# RFCU_V2_0.net
KiCad netlist of a schematic drawn in Altium Designer
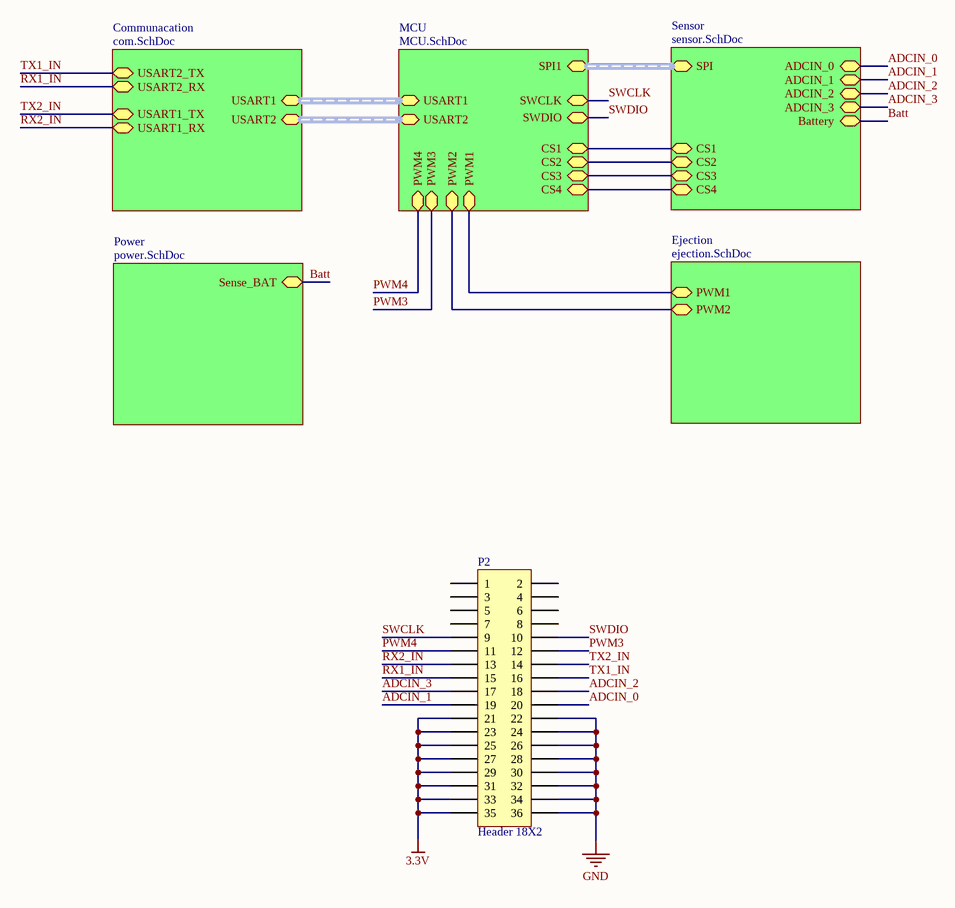
[diagram p0: RFCU_V2.0.SchDoc]

(export (version "E")
  (design (tool "Eeschema 10.0.6"))
  (components
    (comp (ref "P2")
      (value "Header 18X2")
      (footprint "2X18 2.54mm Headers")
      (description "Header, 18-Pin, Dual row")
      (fields (field (name "PUBLISHER") "Altium Limited"))
      (libsource (lib "Miscellaneous Connectors") (part "Header 18X2"))
    )
  )
  (nets
    (net (code "1") (name "/ADCIN_0") (class "Default")
      (node (ref "P2") (pin "20") (pinfunction "20_20") (pintype "passive"))
    )
    (net (code "2") (name "/ADCIN_1") (class "Default")
      (node (ref "P2") (pin "19") (pinfunction "19_19") (pintype "passive"))
    )
    (net (code "3") (name "/ADCIN_2") (class "Default")
      (node (ref "P2") (pin "18") (pinfunction "18_18") (pintype "passive"))
    )
    (net (code "4") (name "/ADCIN_3") (class "Default")
      (node (ref "P2") (pin "17") (pinfunction "17_17") (pintype "passive"))
    )
    (net (code "15") (name "/PWM3") (class "Default")
      (node (ref "P2") (pin "12") (pinfunction "12_12") (pintype "passive"))
    )
    (net (code "16") (name "/PWM4") (class "Default")
      (node (ref "P2") (pin "11") (pinfunction "11_11") (pintype "passive"))
    )
    (net (code "17") (name "/RX1_IN") (class "Default")
      (node (ref "P2") (pin "15") (pinfunction "15_15") (pintype "passive"))
    )
    (net (code "18") (name "/RX2_IN") (class "Default")
      (node (ref "P2") (pin "13") (pinfunction "13_13") (pintype "passive"))
    )
    (net (code "21") (name "/SWCLK") (class "Default")
      (node (ref "P2") (pin "9") (pinfunction "9_9") (pintype "passive"))
    )
    (net (code "22") (name "/SWDIO") (class "Default")
      (node (ref "P2") (pin "10") (pinfunction "10_10") (pintype "passive"))
    )
    (net (code "24") (name "/TX1_IN") (class "Default")
      (node (ref "P2") (pin "16") (pinfunction "16_16") (pintype "passive"))
    )
    (net (code "25") (name "/TX2_IN") (class "Default")
      (node (ref "P2") (pin "14") (pinfunction "14_14") (pintype "passive"))
    )
    (net (code "31") (name "3.3V") (class "Default")
      (node (ref "P2") (pin "21") (pinfunction "21_21") (pintype "passive"))
      (node (ref "P2") (pin "23") (pinfunction "23_23") (pintype "passive"))
      (node (ref "P2") (pin "25") (pinfunction "25_25") (pintype "passive"))
      (node (ref "P2") (pin "27") (pinfunction "27_27") (pintype "passive"))
      (node (ref "P2") (pin "29") (pinfunction "29_29") (pintype "passive"))
      (node (ref "P2") (pin "31") (pinfunction "31_31") (pintype "passive"))
      (node (ref "P2") (pin "33") (pinfunction "33_33") (pintype "passive"))
      (node (ref "P2") (pin "35") (pinfunction "35_35") (pintype "passive"))
    )
    (net (code "32") (name "GND") (class "Default")
      (node (ref "P2") (pin "22") (pinfunction "22_22") (pintype "passive"))
      (node (ref "P2") (pin "24") (pinfunction "24_24") (pintype "passive"))
      (node (ref "P2") (pin "26") (pinfunction "26_26") (pintype "passive"))
      (node (ref "P2") (pin "28") (pinfunction "28_28") (pintype "passive"))
      (node (ref "P2") (pin "30") (pinfunction "30_30") (pintype "passive"))
      (node (ref "P2") (pin "32") (pinfunction "32_32") (pintype "passive"))
      (node (ref "P2") (pin "34") (pinfunction "34_34") (pintype "passive"))
      (node (ref "P2") (pin "36") (pinfunction "36_36") (pintype "passive"))
    )
    (net (code "33") (name "unconnected-(P2-Pad1)") (class "Default")
      (node (ref "P2") (pin "1") (pinfunction "1_1") (pintype "passive"))
    )
    (net (code "34") (name "unconnected-(P2-Pad2)") (class "Default")
      (node (ref "P2") (pin "2") (pinfunction "2_2") (pintype "passive"))
    )
    (net (code "35") (name "unconnected-(P2-Pad3)") (class "Default")
      (node (ref "P2") (pin "3") (pinfunction "3_3") (pintype "passive"))
    )
    (net (code "36") (name "unconnected-(P2-Pad4)") (class "Default")
      (node (ref "P2") (pin "4") (pinfunction "4_4") (pintype "passive"))
    )
    (net (code "37") (name "unconnected-(P2-Pad5)") (class "Default")
      (node (ref "P2") (pin "5") (pinfunction "5_5") (pintype "passive"))
    )
    (net (code "38") (name "unconnected-(P2-Pad6)") (class "Default")
      (node (ref "P2") (pin "6") (pinfunction "6_6") (pintype "passive"))
    )
    (net (code "39") (name "unconnected-(P2-Pad7)") (class "Default")
      (node (ref "P2") (pin "7") (pinfunction "7_7") (pintype "passive"))
    )
    (net (code "40") (name "unconnected-(P2-Pad8)") (class "Default")
      (node (ref "P2") (pin "8") (pinfunction "8_8") (pintype "passive"))
    )
  )
)
